# Schematic_EasyCanad.net
KiCad netlist of a schematic drawn in EasyEDA
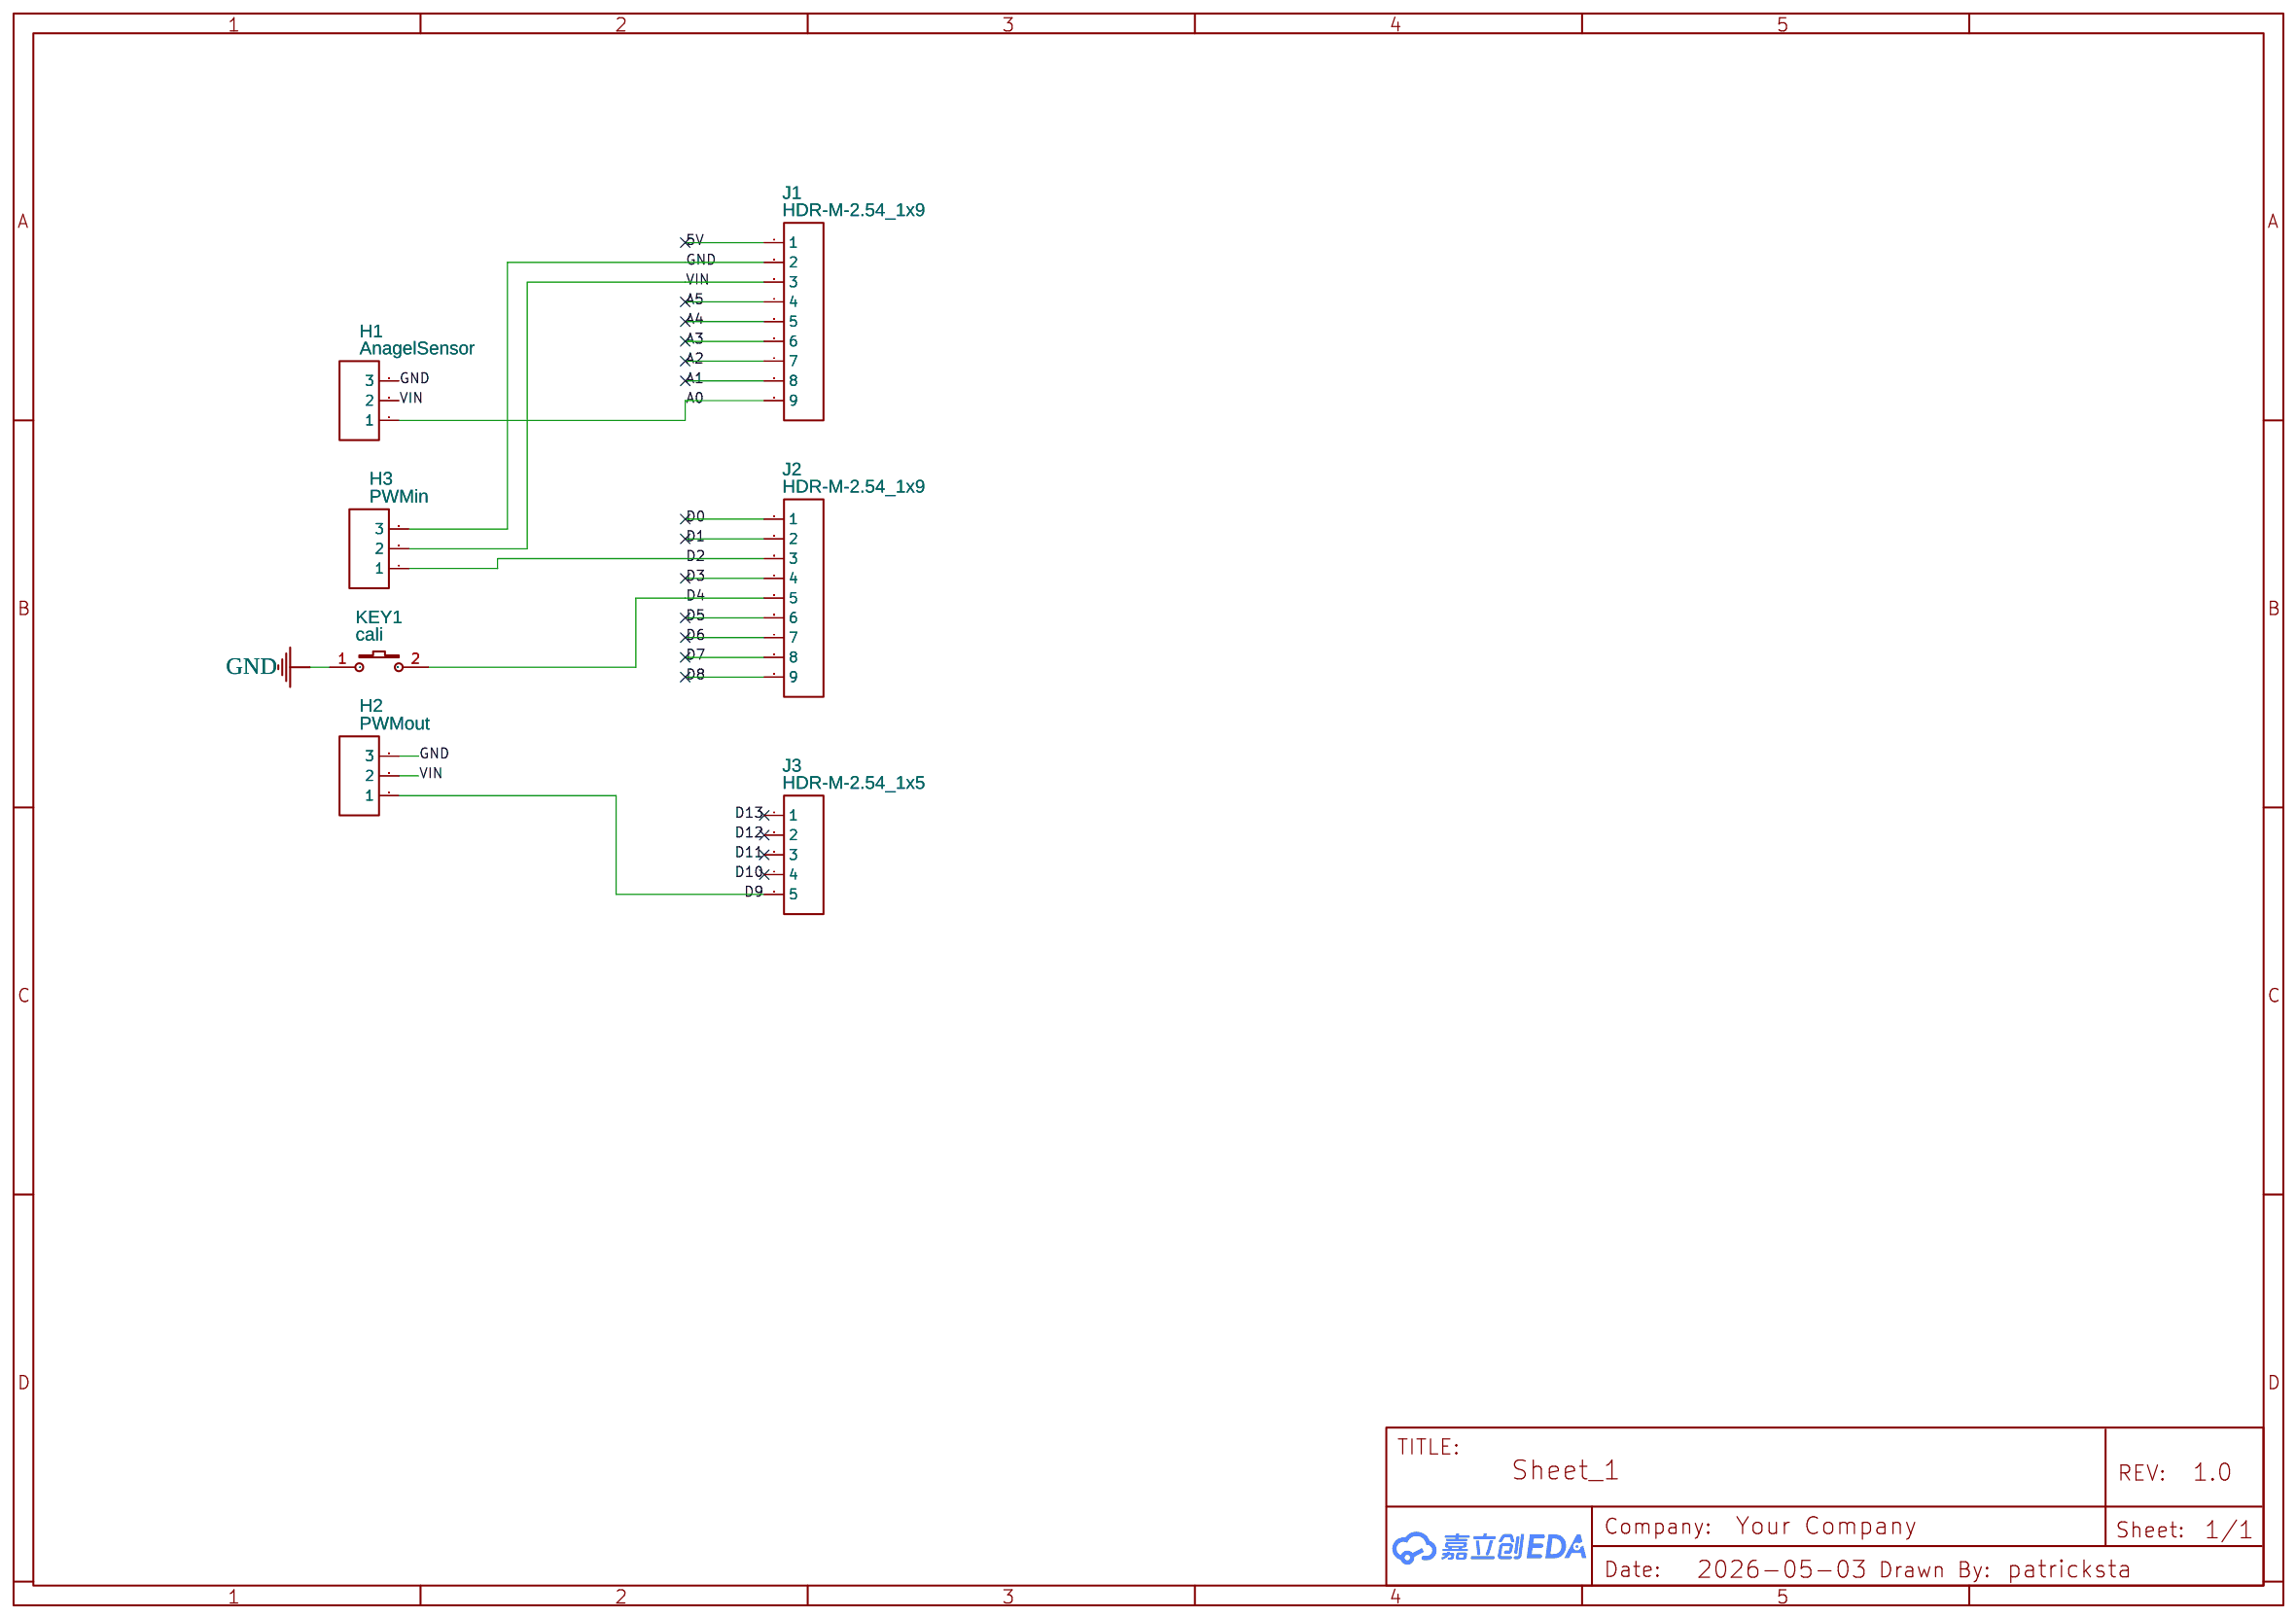
[diagram p0: schematic sheet]

(export (version "E")
  (design (tool "Eeschema 10.0.6"))
  (components
    (comp (ref "H1") (value "AnagelSensor") (libsource (lib "") (part "HDR-F-2.54_1x3")))
    (comp (ref "H2") (value "PWMout") (libsource (lib "") (part "HDR-F-2.54_1x3")))
    (comp (ref "H3") (value "PWMin") (libsource (lib "") (part "HDR-F-2.54_1x3")))
    (comp (ref "J1") (value "HDR-M-2.54_1x9") (libsource (lib "") (part "HDR-M-2.54_1x9")))
    (comp (ref "J2") (value "HDR-M-2.54_1x9") (libsource (lib "") (part "HDR-M-2.54_1x9")))
    (comp (ref "J3") (value "HDR-M-2.54_1x5") (libsource (lib "") (part "HDR-M-2.54_1x5")))
    (comp (ref "KEY1")
      (value "cali")
      (fields (field (name "Manufacturer Part") "K2-1107ST-A4SW-06"))
      (libsource (lib "") (part "K2-3.6×6.1_SMD"))
    )
  )
  (nets
    (net (code "1") (name "/5V") (class "Default")
      (node (ref "J1") (pin "1") (pinfunction "1_1") (pintype "unspecified+no_connect"))
    )
    (net (code "2") (name "/A0") (class "Default")
      (node (ref "H1") (pin "1") (pinfunction "1_1") (pintype "input"))
      (node (ref "J1") (pin "9") (pinfunction "9_9") (pintype "unspecified"))
    )
    (net (code "3") (name "/A1") (class "Default")
      (node (ref "J1") (pin "8") (pinfunction "8_8") (pintype "unspecified+no_connect"))
    )
    (net (code "4") (name "/A2") (class "Default")
      (node (ref "J1") (pin "7") (pinfunction "7_7") (pintype "unspecified+no_connect"))
    )
    (net (code "5") (name "/A3") (class "Default")
      (node (ref "J1") (pin "6") (pinfunction "6_6") (pintype "unspecified+no_connect"))
    )
    (net (code "6") (name "/A4") (class "Default")
      (node (ref "J1") (pin "5") (pinfunction "5_5") (pintype "unspecified+no_connect"))
    )
    (net (code "7") (name "/A5") (class "Default")
      (node (ref "J1") (pin "4") (pinfunction "4_4") (pintype "unspecified+no_connect"))
    )
    (net (code "8") (name "/D0") (class "Default")
      (node (ref "J2") (pin "1") (pinfunction "1_1") (pintype "unspecified+no_connect"))
    )
    (net (code "9") (name "/D1") (class "Default")
      (node (ref "J2") (pin "2") (pinfunction "2_2") (pintype "unspecified+no_connect"))
    )
    (net (code "10") (name "/D2") (class "Default")
      (node (ref "H3") (pin "1") (pinfunction "1_1") (pintype "input"))
      (node (ref "J2") (pin "3") (pinfunction "3_3") (pintype "unspecified"))
    )
    (net (code "11") (name "/D3") (class "Default")
      (node (ref "J2") (pin "4") (pinfunction "4_4") (pintype "unspecified+no_connect"))
    )
    (net (code "12") (name "/D4") (class "Default")
      (node (ref "J2") (pin "5") (pinfunction "5_5") (pintype "unspecified"))
      (node (ref "KEY1") (pin "2") (pinfunction "2_2") (pintype "unspecified"))
    )
    (net (code "13") (name "/D5") (class "Default")
      (node (ref "J2") (pin "6") (pinfunction "6_6") (pintype "unspecified+no_connect"))
    )
    (net (code "14") (name "/D6") (class "Default")
      (node (ref "J2") (pin "7") (pinfunction "7_7") (pintype "unspecified+no_connect"))
    )
    (net (code "15") (name "/D7") (class "Default")
      (node (ref "J2") (pin "8") (pinfunction "8_8") (pintype "unspecified+no_connect"))
    )
    (net (code "16") (name "/D8") (class "Default")
      (node (ref "J2") (pin "9") (pinfunction "9_9") (pintype "unspecified+no_connect"))
    )
    (net (code "17") (name "/D9") (class "Default")
      (node (ref "H2") (pin "1") (pinfunction "1_1") (pintype "input"))
      (node (ref "J3") (pin "5") (pinfunction "5_5") (pintype "unspecified"))
    )
    (net (code "18") (name "/D10") (class "Default")
      (node (ref "J3") (pin "4") (pinfunction "4_4") (pintype "unspecified+no_connect"))
    )
    (net (code "19") (name "/D11") (class "Default")
      (node (ref "J3") (pin "3") (pinfunction "3_3") (pintype "unspecified+no_connect"))
    )
    (net (code "20") (name "/D12") (class "Default")
      (node (ref "J3") (pin "2") (pinfunction "2_2") (pintype "unspecified+no_connect"))
    )
    (net (code "21") (name "/D13") (class "Default")
      (node (ref "J3") (pin "1") (pinfunction "1_1") (pintype "unspecified+no_connect"))
    )
    (net (code "22") (name "/VIN") (class "Default")
      (node (ref "H1") (pin "2") (pinfunction "2_2") (pintype "input"))
      (node (ref "H2") (pin "2") (pinfunction "2_2") (pintype "input"))
      (node (ref "H3") (pin "2") (pinfunction "2_2") (pintype "input"))
      (node (ref "J1") (pin "3") (pinfunction "3_3") (pintype "unspecified"))
    )
    (net (code "23") (name "GND") (class "Default")
      (node (ref "H1") (pin "3") (pinfunction "3_3") (pintype "input"))
      (node (ref "H2") (pin "3") (pinfunction "3_3") (pintype "input"))
      (node (ref "H3") (pin "3") (pinfunction "3_3") (pintype "input"))
      (node (ref "J1") (pin "2") (pinfunction "2_2") (pintype "unspecified"))
      (node (ref "KEY1") (pin "1") (pinfunction "1_1") (pintype "unspecified"))
    )
  )
)
